# lnrc_basico_edu.net
KiCad netlist of a schematic drawn in EAGLE
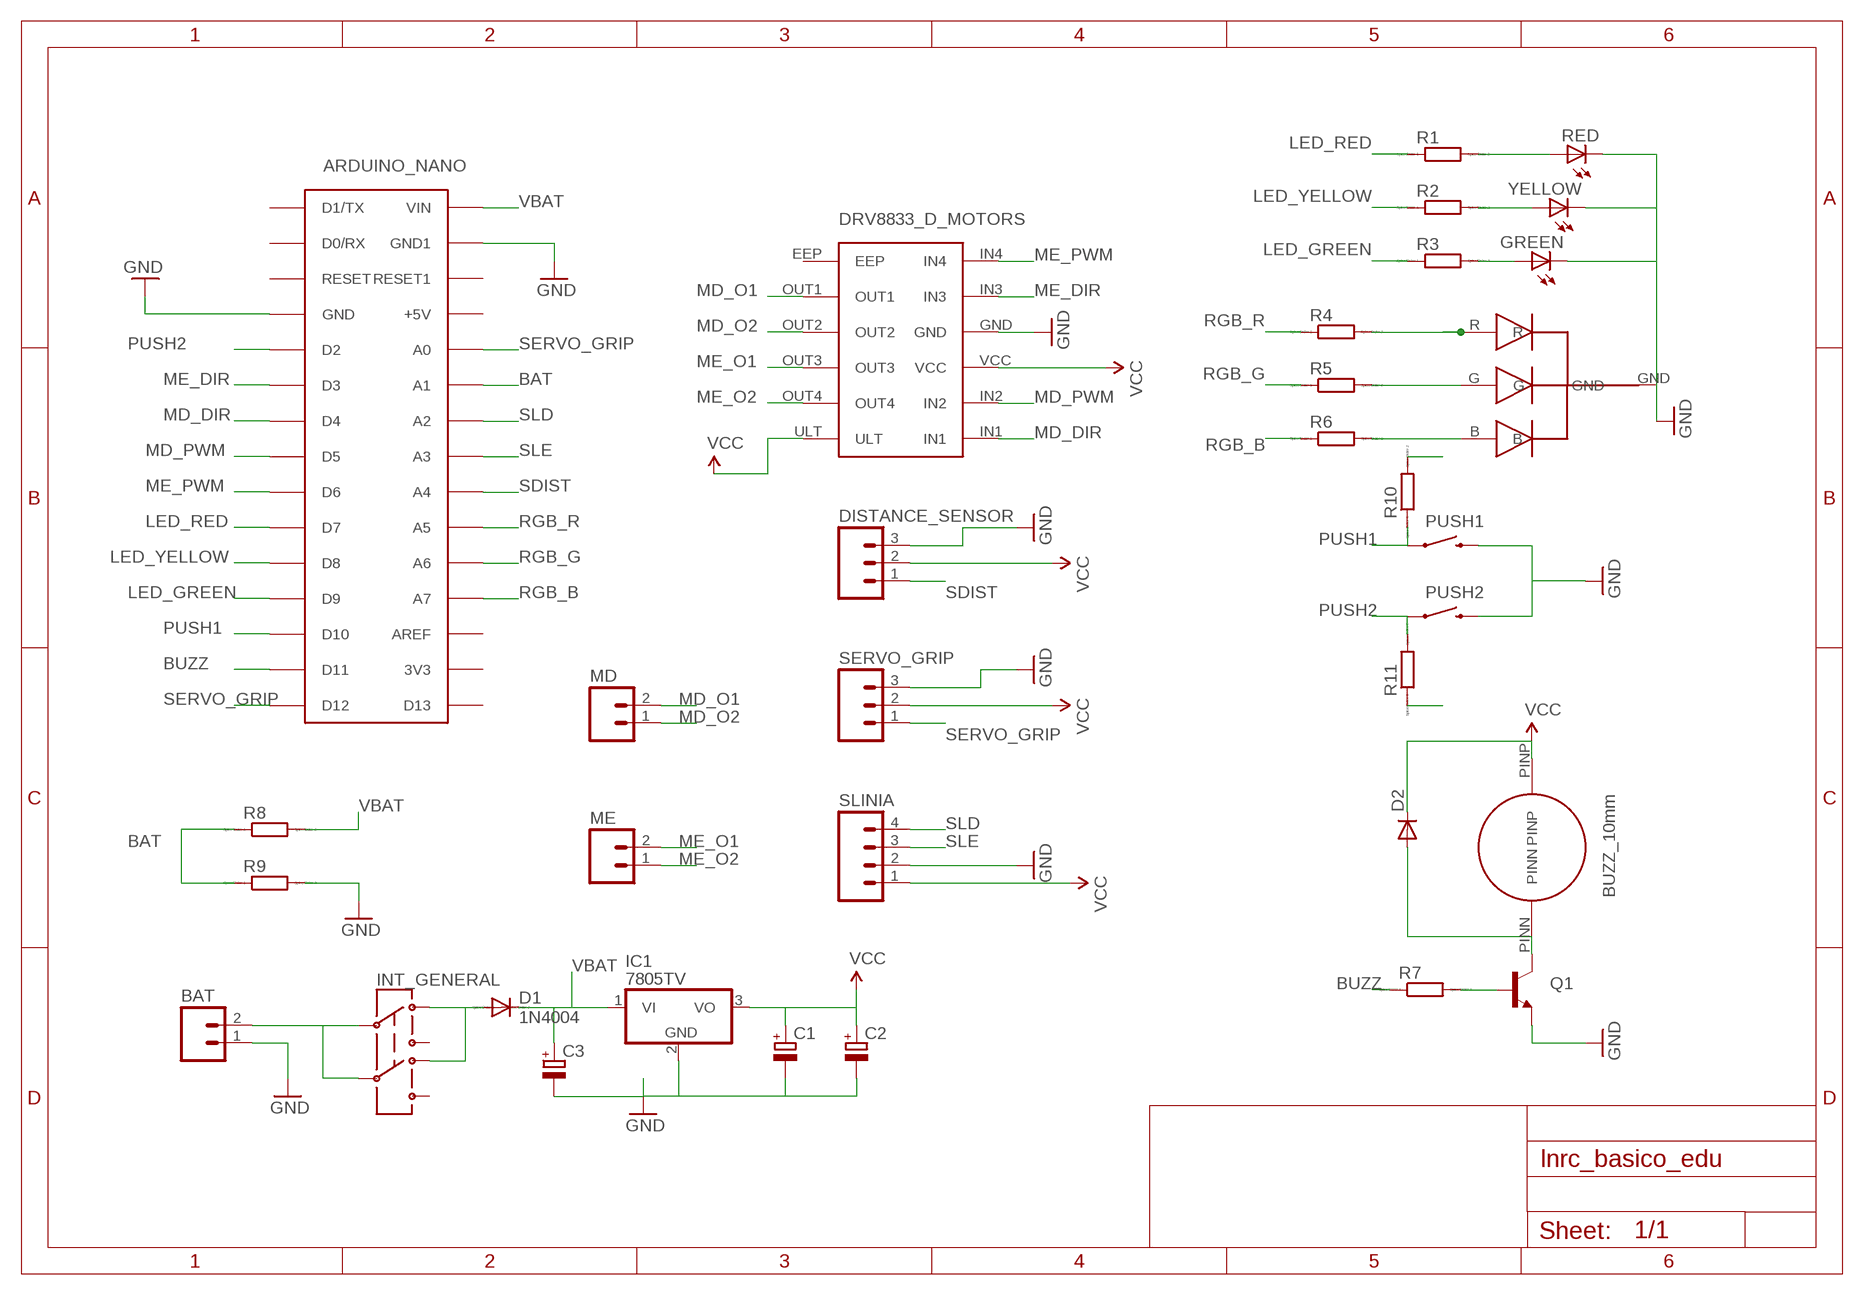
[diagram p0: schematic, sheet 1]

(export (version "E")
  (design (tool "Eeschema 10.0.6"))
  (components
    (comp (ref "ARDUINO_NANO")
      (value "ARDUINONANO")
      (footprint "eagle-import:PDIP-32")
      (libsource (lib "eagle-import") (part "ARDUINONANO"))
    )
    (comp (ref "BAT")
      (value "M02LOCK_LONGPADS")
      (footprint "eagle-import:1X02_LOCK_LONGPADS")
      (libsource (lib "eagle-import") (part "M02LOCK_LONGPADS"))
    )
    (comp (ref "C1")
      (value "CPOL-EUE2.5-6")
      (footprint "eagle-import:E2,5-6")
      (libsource (lib "eagle-import") (part "CPOL-EUE2.5-6"))
    )
    (comp (ref "C2")
      (value "CPOL-EUE2.5-6")
      (footprint "eagle-import:E2,5-6")
      (libsource (lib "eagle-import") (part "CPOL-EUE2.5-6"))
    )
    (comp (ref "C3")
      (value "CPOL-EUE2.5-6")
      (footprint "eagle-import:E2,5-6")
      (libsource (lib "eagle-import") (part "CPOL-EUE2.5-6"))
    )
    (comp (ref "D1")
      (value "1N4004")
      (footprint "eagle-import:DO41-10")
      (libsource (lib "eagle-import") (part "1N4004"))
    )
    (comp (ref "D2")
      (value "DIODE1N4148")
      (footprint "eagle-import:DIODE-1N4148")
      (libsource (lib "eagle-import") (part "DIODE1N4148"))
    )
    (comp (ref "DISTANCE_SENSOR")
      (value "M03LONGPADS")
      (footprint "eagle-import:1X03_LONGPADS")
      (libsource (lib "eagle-import") (part "M03LONGPADS"))
    )
    (comp (ref "DRV8833_D_MOTORS")
      (value "DRV8833_BREAKOUT")
      (footprint "eagle-import:DRV8833_BREAKOUT")
      (libsource (lib "eagle-import") (part "DRV8833_BREAKOUT"))
    )
    (comp (ref "GREEN")
      (value "LED3MM")
      (footprint "eagle-import:LED3MM")
      (libsource (lib "eagle-import") (part "LED3MM"))
    )
    (comp (ref "IC1")
      (value "7805TV")
      (footprint "eagle-import:TO220V")
      (libsource (lib "eagle-import") (part "78TV05"))
    )
    (comp (ref "INT_GENERAL")
      (value "AYZ0202_TH")
      (footprint "eagle-import:AYZ0202_TH")
      (libsource (lib "eagle-import") (part "AYZ0202_TH"))
    )
    (comp (ref "MD")
      (value "M02")
      (footprint "eagle-import:02P")
      (libsource (lib "eagle-import") (part "M02"))
    )
    (comp (ref "ME")
      (value "M02")
      (footprint "eagle-import:02P")
      (libsource (lib "eagle-import") (part "M02"))
    )
    (comp (ref "PUSH1")
      (value "SWITCH-MOMENTARY-2PTH")
      (footprint "eagle-import:TACTILE-PTH")
      (libsource (lib "eagle-import") (part "SWITCH-MOMENTARY-2PTH"))
    )
    (comp (ref "PUSH2")
      (value "SWITCH-MOMENTARY-2PTH")
      (footprint "eagle-import:TACTILE-PTH")
      (libsource (lib "eagle-import") (part "SWITCH-MOMENTARY-2PTH"))
    )
    (comp (ref "Q1")
      (value "TRANSISTOR_NPNBC547")
      (footprint "eagle-import:TO-92-AMMO")
      (libsource (lib "eagle-import") (part "TRANSISTOR_NPNBC547"))
    )
    (comp (ref "R1")
      (value "R-EU_0309_10")
      (footprint "eagle-import:0309_10")
      (libsource (lib "eagle-import") (part "R-EU_0309_10"))
    )
    (comp (ref "R2")
      (value "R-EU_0309_10")
      (footprint "eagle-import:0309_10")
      (libsource (lib "eagle-import") (part "R-EU_0309_10"))
    )
    (comp (ref "R3")
      (value "R-EU_0309_10")
      (footprint "eagle-import:0309_10")
      (libsource (lib "eagle-import") (part "R-EU_0309_10"))
    )
    (comp (ref "R4")
      (value "R-EU_0309_10")
      (footprint "eagle-import:0309_10")
      (libsource (lib "eagle-import") (part "R-EU_0309_10"))
    )
    (comp (ref "R5")
      (value "R-EU_0309_10")
      (footprint "eagle-import:0309_10")
      (libsource (lib "eagle-import") (part "R-EU_0309_10"))
    )
    (comp (ref "R6")
      (value "R-EU_0309_10")
      (footprint "eagle-import:0309_10")
      (libsource (lib "eagle-import") (part "R-EU_0309_10"))
    )
    (comp (ref "R7")
      (value "R-EU_0309_10")
      (footprint "eagle-import:0309_10")
      (libsource (lib "eagle-import") (part "R-EU_0309_10"))
    )
    (comp (ref "R8")
      (value "R-EU_0309_10")
      (footprint "eagle-import:0309_10")
      (libsource (lib "eagle-import") (part "R-EU_0309_10"))
    )
    (comp (ref "R9")
      (value "R-EU_0309_10")
      (footprint "eagle-import:0309_10")
      (libsource (lib "eagle-import") (part "R-EU_0309_10"))
    )
    (comp (ref "R10")
      (value "R-EU_0309_10")
      (footprint "eagle-import:0309_10")
      (libsource (lib "eagle-import") (part "R-EU_0309_10"))
    )
    (comp (ref "R11")
      (value "R-EU_0309_10")
      (footprint "eagle-import:0309_10")
      (libsource (lib "eagle-import") (part "R-EU_0309_10"))
    )
    (comp (ref "RED")
      (value "LED3MM")
      (footprint "eagle-import:LED3MM")
      (libsource (lib "eagle-import") (part "LED3MM"))
    )
    (comp (ref "SERVO_GRIP")
      (value "M03LONGPADS")
      (footprint "eagle-import:1X03_LONGPADS")
      (libsource (lib "eagle-import") (part "M03LONGPADS"))
    )
    (comp (ref "SLINIA")
      (value "M04LONGPADS")
      (footprint "eagle-import:1X04_LONGPADS")
      (libsource (lib "eagle-import") (part "M04LONGPADS"))
    )
    (comp (ref "U$1")
      (value "BUZZ_10MM")
      (footprint "eagle-import:BUZZ_10MM")
      (libsource (lib "eagle-import") (part "BUZZ_10MM"))
    )
    (comp (ref "U$2")
      (value "LED_RGB_COMCATH")
      (footprint "eagle-import:LED_RGB_COMMCATH")
      (libsource (lib "eagle-import") (part "LED_RGB_COMCATH"))
    )
    (comp (ref "YELLOW")
      (value "LED3MM")
      (footprint "eagle-import:LED3MM")
      (libsource (lib "eagle-import") (part "LED3MM"))
    )
  )
  (nets
    (net (code "1") (name "/BAT") (class "Default")
      (node (ref "ARDUINO_NANO") (pin "A1") (pinfunction "A1_A1") (pintype "bidirectional"))
      (node (ref "R8") (pin "1") (pinfunction "1_1") (pintype "passive"))
      (node (ref "R9") (pin "1") (pinfunction "1_1") (pintype "passive"))
    )
    (net (code "2") (name "/BUZZ") (class "Default")
      (node (ref "ARDUINO_NANO") (pin "D11") (pinfunction "D11_D11") (pintype "bidirectional"))
      (node (ref "R7") (pin "1") (pinfunction "1_1") (pintype "passive"))
    )
    (net (code "3") (name "/LED_GREEN") (class "Default")
      (node (ref "ARDUINO_NANO") (pin "D9") (pinfunction "D9_D9") (pintype "bidirectional"))
      (node (ref "R3") (pin "1") (pinfunction "1_1") (pintype "passive"))
    )
    (net (code "4") (name "/LED_RED") (class "Default")
      (node (ref "ARDUINO_NANO") (pin "D7") (pinfunction "D7_D7") (pintype "bidirectional"))
      (node (ref "R1") (pin "1") (pinfunction "1_1") (pintype "passive"))
    )
    (net (code "5") (name "/LED_YELLOW") (class "Default")
      (node (ref "ARDUINO_NANO") (pin "D8") (pinfunction "D8_D8") (pintype "bidirectional"))
      (node (ref "R2") (pin "1") (pinfunction "1_1") (pintype "passive"))
    )
    (net (code "6") (name "/MD_DIR") (class "Default")
      (node (ref "ARDUINO_NANO") (pin "D4") (pinfunction "D4_D4") (pintype "bidirectional"))
      (node (ref "DRV8833_D_MOTORS") (pin "IN1") (pinfunction "IN1_IN1") (pintype "bidirectional"))
    )
    (net (code "7") (name "/MD_O1") (class "Default")
      (node (ref "DRV8833_D_MOTORS") (pin "OUT1") (pinfunction "OUT1_OUT1") (pintype "bidirectional"))
      (node (ref "MD") (pin "2") (pinfunction "2_2") (pintype "passive"))
    )
    (net (code "8") (name "/MD_O2") (class "Default")
      (node (ref "DRV8833_D_MOTORS") (pin "OUT2") (pinfunction "OUT2_OUT2") (pintype "bidirectional"))
      (node (ref "MD") (pin "1") (pinfunction "1_1") (pintype "passive"))
    )
    (net (code "9") (name "/MD_PWM") (class "Default")
      (node (ref "ARDUINO_NANO") (pin "D5") (pinfunction "D5_D5") (pintype "bidirectional"))
      (node (ref "DRV8833_D_MOTORS") (pin "IN2") (pinfunction "IN2_IN2") (pintype "bidirectional"))
    )
    (net (code "10") (name "/ME_DIR") (class "Default")
      (node (ref "ARDUINO_NANO") (pin "D3") (pinfunction "D3_D3") (pintype "bidirectional"))
      (node (ref "DRV8833_D_MOTORS") (pin "IN3") (pinfunction "IN3_IN3") (pintype "bidirectional"))
    )
    (net (code "11") (name "/ME_O1") (class "Default")
      (node (ref "DRV8833_D_MOTORS") (pin "OUT3") (pinfunction "OUT3_OUT3") (pintype "bidirectional"))
      (node (ref "ME") (pin "2") (pinfunction "2_2") (pintype "passive"))
    )
    (net (code "12") (name "/ME_O2") (class "Default")
      (node (ref "DRV8833_D_MOTORS") (pin "OUT4") (pinfunction "OUT4_OUT4") (pintype "bidirectional"))
      (node (ref "ME") (pin "1") (pinfunction "1_1") (pintype "passive"))
    )
    (net (code "13") (name "/ME_PWM") (class "Default")
      (node (ref "ARDUINO_NANO") (pin "D6") (pinfunction "D6_D6") (pintype "bidirectional"))
      (node (ref "DRV8833_D_MOTORS") (pin "IN4") (pinfunction "IN4_IN4") (pintype "bidirectional"))
    )
    (net (code "14") (name "/PUSH1") (class "Default")
      (node (ref "ARDUINO_NANO") (pin "D10") (pinfunction "D10_D10") (pintype "bidirectional"))
      (node (ref "PUSH1") (pin "1") (pinfunction "1_1") (pintype "passive"))
      (node (ref "R10") (pin "1") (pinfunction "1_1") (pintype "passive"))
    )
    (net (code "15") (name "/PUSH2") (class "Default")
      (node (ref "ARDUINO_NANO") (pin "D2") (pinfunction "D2_D2") (pintype "bidirectional"))
      (node (ref "PUSH2") (pin "1") (pinfunction "1_1") (pintype "passive"))
      (node (ref "R11") (pin "2") (pinfunction "2_2") (pintype "passive"))
    )
    (net (code "16") (name "/RGB_B") (class "Default")
      (node (ref "ARDUINO_NANO") (pin "A7") (pinfunction "A7_A7") (pintype "bidirectional"))
      (node (ref "R6") (pin "1") (pinfunction "1_1") (pintype "passive"))
    )
    (net (code "17") (name "/RGB_G") (class "Default")
      (node (ref "ARDUINO_NANO") (pin "A6") (pinfunction "A6_A6") (pintype "bidirectional"))
      (node (ref "R5") (pin "1") (pinfunction "1_1") (pintype "passive"))
    )
    (net (code "18") (name "/RGB_R") (class "Default")
      (node (ref "ARDUINO_NANO") (pin "A5") (pinfunction "A5_A5") (pintype "bidirectional"))
      (node (ref "R4") (pin "1") (pinfunction "1_1") (pintype "passive"))
    )
    (net (code "19") (name "/SDIST") (class "Default")
      (node (ref "ARDUINO_NANO") (pin "A4") (pinfunction "A4_A4") (pintype "bidirectional"))
      (node (ref "DISTANCE_SENSOR") (pin "1") (pinfunction "1_1") (pintype "passive"))
    )
    (net (code "20") (name "/SERVO_GRIP") (class "Default")
      (node (ref "ARDUINO_NANO") (pin "A0") (pinfunction "A0_A0") (pintype "bidirectional"))
      (node (ref "ARDUINO_NANO") (pin "D12") (pinfunction "D12_D12") (pintype "bidirectional"))
      (node (ref "SERVO_GRIP") (pin "1") (pinfunction "1_1") (pintype "passive"))
    )
    (net (code "21") (name "/SLD") (class "Default")
      (node (ref "ARDUINO_NANO") (pin "A2") (pinfunction "A2_A2") (pintype "bidirectional"))
      (node (ref "SLINIA") (pin "4") (pinfunction "4_4") (pintype "passive"))
    )
    (net (code "22") (name "/SLE") (class "Default")
      (node (ref "ARDUINO_NANO") (pin "A3") (pinfunction "A3_A3") (pintype "bidirectional"))
      (node (ref "SLINIA") (pin "3") (pinfunction "3_3") (pintype "passive"))
    )
    (net (code "23") (name "/VBAT") (class "Default")
      (node (ref "ARDUINO_NANO") (pin "VIN") (pinfunction "VIN_VIN") (pintype "bidirectional"))
      (node (ref "C3") (pin "+") (pinfunction "+_+") (pintype "passive"))
      (node (ref "D1") (pin "C") (pinfunction "C_C") (pintype "passive"))
      (node (ref "IC1") (pin "1") (pinfunction "VI_1") (pintype "input"))
      (node (ref "R8") (pin "2") (pinfunction "2_2") (pintype "passive"))
    )
    (net (code "24") (name "GND") (class "Default")
      (node (ref "ARDUINO_NANO") (pin "GND") (pinfunction "GND_GND") (pintype "bidirectional"))
      (node (ref "ARDUINO_NANO") (pin "GND1") (pinfunction "GND1_GND1") (pintype "bidirectional"))
      (node (ref "BAT") (pin "1") (pinfunction "1_1") (pintype "passive"))
      (node (ref "C1") (pin "-") (pinfunction "-_-") (pintype "passive"))
      (node (ref "C2") (pin "-") (pinfunction "-_-") (pintype "passive"))
      (node (ref "C3") (pin "-") (pinfunction "-_-") (pintype "passive"))
      (node (ref "DISTANCE_SENSOR") (pin "3") (pinfunction "3_3") (pintype "passive"))
      (node (ref "DRV8833_D_MOTORS") (pin "GND") (pinfunction "GND_GND") (pintype "bidirectional"))
      (node (ref "GREEN") (pin "K") (pinfunction "C_K") (pintype "passive"))
      (node (ref "IC1") (pin "2") (pinfunction "GND_2") (pintype "passive"))
      (node (ref "PUSH1") (pin "3") (pinfunction "2_3") (pintype "passive"))
      (node (ref "PUSH2") (pin "3") (pinfunction "2_3") (pintype "passive"))
      (node (ref "Q1") (pin "3") (pinfunction "E_3") (pintype "passive"))
      (node (ref "R9") (pin "2") (pinfunction "2_2") (pintype "passive"))
      (node (ref "RED") (pin "K") (pinfunction "C_K") (pintype "passive"))
      (node (ref "SERVO_GRIP") (pin "3") (pinfunction "3_3") (pintype "passive"))
      (node (ref "SLINIA") (pin "2") (pinfunction "2_2") (pintype "passive"))
      (node (ref "U$2") (pin "GND") (pinfunction "GND_GND") (pintype "bidirectional"))
      (node (ref "YELLOW") (pin "K") (pinfunction "C_K") (pintype "passive"))
    )
    (net (code "25") (name "Net-(BAT-Pad2)") (class "Default")
      (node (ref "BAT") (pin "2") (pinfunction "2_2") (pintype "passive"))
      (node (ref "INT_GENERAL") (pin "C1") (pinfunction "C1_C1") (pintype "bidirectional"))
      (node (ref "INT_GENERAL") (pin "C2") (pinfunction "C2_C2") (pintype "bidirectional"))
    )
    (net (code "26") (name "Net-(D1-PadA)") (class "Default")
      (node (ref "D1") (pin "A") (pinfunction "A_A") (pintype "passive"))
      (node (ref "INT_GENERAL") (pin "D1") (pinfunction "D1_D1") (pintype "bidirectional"))
      (node (ref "INT_GENERAL") (pin "D2") (pinfunction "D2_D2") (pintype "bidirectional"))
    )
    (net (code "27") (name "Net-(GREEN-PadA)") (class "Default")
      (node (ref "GREEN") (pin "A") (pinfunction "A_A") (pintype "passive"))
      (node (ref "R3") (pin "2") (pinfunction "2_2") (pintype "passive"))
    )
    (net (code "28") (name "Net-(Q1-B)") (class "Default")
      (node (ref "Q1") (pin "2") (pinfunction "B_2") (pintype "passive"))
      (node (ref "R7") (pin "2") (pinfunction "2_2") (pintype "passive"))
    )
    (net (code "29") (name "Net-(Q1-C)") (class "Default")
      (node (ref "D2") (pin "A") (pinfunction "A_A") (pintype "passive"))
      (node (ref "Q1") (pin "1") (pinfunction "C_1") (pintype "passive"))
      (node (ref "U$1") (pin "PINN") (pinfunction "PINN_PINN") (pintype "bidirectional"))
    )
    (net (code "30") (name "Net-(R1-Pad2)") (class "Default")
      (node (ref "R1") (pin "2") (pinfunction "2_2") (pintype "passive"))
      (node (ref "RED") (pin "A") (pinfunction "A_A") (pintype "passive"))
    )
    (net (code "31") (name "Net-(R2-Pad2)") (class "Default")
      (node (ref "R2") (pin "2") (pinfunction "2_2") (pintype "passive"))
      (node (ref "YELLOW") (pin "A") (pinfunction "A_A") (pintype "passive"))
    )
    (net (code "32") (name "Net-(R4-Pad2)") (class "Default")
      (node (ref "R4") (pin "2") (pinfunction "2_2") (pintype "passive"))
      (node (ref "U$2") (pin "R") (pinfunction "R_R") (pintype "bidirectional"))
    )
    (net (code "33") (name "Net-(R5-Pad2)") (class "Default")
      (node (ref "R5") (pin "2") (pinfunction "2_2") (pintype "passive"))
      (node (ref "U$2") (pin "G") (pinfunction "G_G") (pintype "bidirectional"))
    )
    (net (code "34") (name "Net-(R6-Pad2)") (class "Default")
      (node (ref "R6") (pin "2") (pinfunction "2_2") (pintype "passive"))
      (node (ref "U$2") (pin "B") (pinfunction "B_B") (pintype "bidirectional"))
    )
    (net (code "35") (name "VCC") (class "Default")
      (node (ref "C1") (pin "+") (pinfunction "+_+") (pintype "passive"))
      (node (ref "C2") (pin "+") (pinfunction "+_+") (pintype "passive"))
      (node (ref "D2") (pin "C") (pinfunction "C_C") (pintype "passive"))
      (node (ref "DISTANCE_SENSOR") (pin "2") (pinfunction "2_2") (pintype "passive"))
      (node (ref "DRV8833_D_MOTORS") (pin "ULT") (pinfunction "ULT_ULT") (pintype "bidirectional"))
      (node (ref "DRV8833_D_MOTORS") (pin "VCC") (pinfunction "VCC_VCC") (pintype "bidirectional"))
      (node (ref "IC1") (pin "3") (pinfunction "VO_3") (pintype "passive"))
      (node (ref "R10") (pin "2") (pinfunction "2_2") (pintype "passive"))
      (node (ref "R11") (pin "1") (pinfunction "1_1") (pintype "passive"))
      (node (ref "SERVO_GRIP") (pin "2") (pinfunction "2_2") (pintype "passive"))
      (node (ref "SLINIA") (pin "1") (pinfunction "1_1") (pintype "passive"))
      (node (ref "U$1") (pin "PINP") (pinfunction "PINP_PINP") (pintype "bidirectional"))
    )
    (net (code "36") (name "unconnected-(ARDUINO_NANO-Pad+5V)") (class "Default")
      (node (ref "ARDUINO_NANO") (pin "+5V") (pinfunction "+5V_+5V") (pintype "bidirectional"))
    )
    (net (code "37") (name "unconnected-(ARDUINO_NANO-Pad3V3)") (class "Default")
      (node (ref "ARDUINO_NANO") (pin "3V3") (pinfunction "3V3_3V3") (pintype "bidirectional"))
    )
    (net (code "38") (name "unconnected-(ARDUINO_NANO-PadAREF)") (class "Default")
      (node (ref "ARDUINO_NANO") (pin "AREF") (pinfunction "AREF_AREF") (pintype "bidirectional"))
    )
    (net (code "39") (name "unconnected-(ARDUINO_NANO-PadD0{slash}RX)") (class "Default")
      (node (ref "ARDUINO_NANO") (pin "D0/RX") (pinfunction "D0/RX_D0/RX") (pintype "bidirectional"))
    )
    (net (code "40") (name "unconnected-(ARDUINO_NANO-PadD1{slash}TX)") (class "Default")
      (node (ref "ARDUINO_NANO") (pin "D1/TX") (pinfunction "D1/TX_D1/TX") (pintype "bidirectional"))
    )
    (net (code "41") (name "unconnected-(ARDUINO_NANO-PadD13)") (class "Default")
      (node (ref "ARDUINO_NANO") (pin "D13") (pinfunction "D13_D13") (pintype "bidirectional"))
    )
    (net (code "42") (name "unconnected-(ARDUINO_NANO-PadRESET)") (class "Default")
      (node (ref "ARDUINO_NANO") (pin "RESET") (pinfunction "RESET_RESET") (pintype "bidirectional"))
    )
    (net (code "43") (name "unconnected-(ARDUINO_NANO-PadRESET1)") (class "Default")
      (node (ref "ARDUINO_NANO") (pin "RESET1") (pinfunction "RESET1_RESET1") (pintype "bidirectional"))
    )
    (net (code "44") (name "unconnected-(DRV8833_D_MOTORS-PadEEP)") (class "Default")
      (node (ref "DRV8833_D_MOTORS") (pin "EEP") (pinfunction "EEP_EEP") (pintype "bidirectional"))
    )
    (net (code "45") (name "unconnected-(INT_GENERAL-PadB1)") (class "Default")
      (node (ref "INT_GENERAL") (pin "B1") (pinfunction "B1_B1") (pintype "bidirectional"))
    )
    (net (code "46") (name "unconnected-(INT_GENERAL-PadB2)") (class "Default")
      (node (ref "INT_GENERAL") (pin "B2") (pinfunction "B2_B2") (pintype "bidirectional"))
    )
  )
)
